# Spartan3_TestBoard_3.net
KiCad netlist of a schematic drawn in Altium Designer
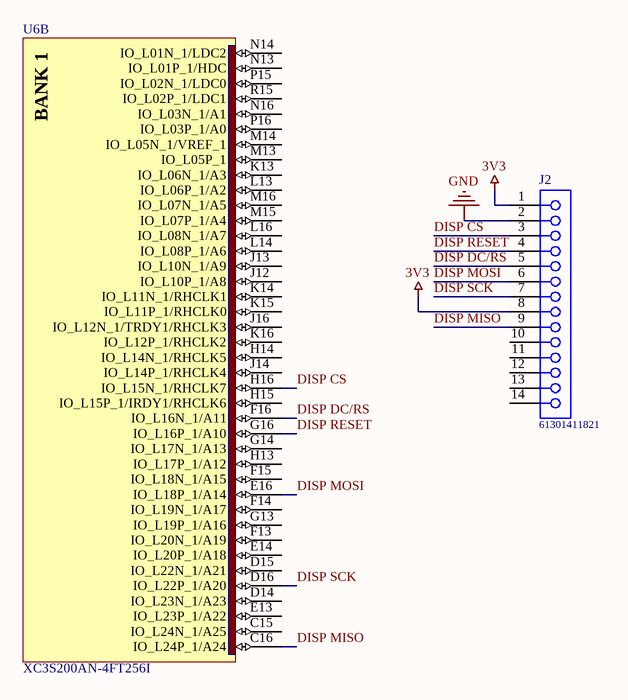
[diagram p0: Spartan3_TestBoard_3.SchDoc]

(export (version "E")
  (design (tool "Eeschema 10.0.6"))
  (components
    (comp (ref "J2")
      (value "61301411821")
      (footprint "61301411821")
      (description "WR-PHD Socket Header, THT, pitch 2.54mm, Single Row, Vertical, 14p")
      (fields (field (name "MANUFACTURER") "Wurth Elektronik"))
      (libsource (lib "61300311021_Altium_WR-PHD_rev20a") (part "61301411821"))
    )
    (comp (ref "U6")
      (value "XC3S200AN-4FT256I")
      (footprint "XC3S200AN-4FT256I")
      (libsource (lib "XC3S200AN-4FT256I") (part "XC3S200AN-4FT256I"))
    )
  )
  (nets
    (net (code "1") (name "/DISP CS") (class "Default")
      (node (ref "J2") (pin "3") (pinfunction "3_3") (pintype "passive"))
      (node (ref "U6") (pin "H16") (pinfunction "IO_L15N_1/RHCLK7_H16") (pintype "bidirectional"))
    )
    (net (code "2") (name "/DISP DC{slash}RS") (class "Default")
      (node (ref "J2") (pin "5") (pinfunction "5_5") (pintype "passive"))
      (node (ref "U6") (pin "F16") (pinfunction "IO_L16N_1/A11_F16") (pintype "bidirectional"))
    )
    (net (code "3") (name "/DISP MISO") (class "Default")
      (node (ref "J2") (pin "9") (pinfunction "9_9") (pintype "passive"))
      (node (ref "U6") (pin "C16") (pinfunction "IO_L24P_1/A24_C16") (pintype "bidirectional"))
    )
    (net (code "4") (name "/DISP MOSI") (class "Default")
      (node (ref "J2") (pin "6") (pinfunction "6_6") (pintype "passive"))
      (node (ref "U6") (pin "E16") (pinfunction "IO_L18P_1/A14_E16") (pintype "bidirectional"))
    )
    (net (code "5") (name "/DISP RESET") (class "Default")
      (node (ref "J2") (pin "4") (pinfunction "4_4") (pintype "passive"))
      (node (ref "U6") (pin "G16") (pinfunction "IO_L16P_1/A10_G16") (pintype "bidirectional"))
    )
    (net (code "6") (name "/DISP SCK") (class "Default")
      (node (ref "J2") (pin "7") (pinfunction "7_7") (pintype "passive"))
      (node (ref "U6") (pin "D16") (pinfunction "IO_L22P_1/A20_D16") (pintype "bidirectional"))
    )
    (net (code "7") (name "3V3") (class "Default")
      (node (ref "J2") (pin "1") (pinfunction "1_1") (pintype "passive"))
      (node (ref "J2") (pin "8") (pinfunction "8_8") (pintype "passive"))
    )
    (net (code "8") (name "GND") (class "Default")
      (node (ref "J2") (pin "2") (pinfunction "2_2") (pintype "passive"))
    )
    (net (code "9") (name "unconnected-(J2-Pad10)") (class "Default")
      (node (ref "J2") (pin "10") (pinfunction "10_10") (pintype "passive"))
    )
    (net (code "10") (name "unconnected-(J2-Pad11)") (class "Default")
      (node (ref "J2") (pin "11") (pinfunction "11_11") (pintype "passive"))
    )
    (net (code "11") (name "unconnected-(J2-Pad12)") (class "Default")
      (node (ref "J2") (pin "12") (pinfunction "12_12") (pintype "passive"))
    )
    (net (code "12") (name "unconnected-(J2-Pad13)") (class "Default")
      (node (ref "J2") (pin "13") (pinfunction "13_13") (pintype "passive"))
    )
    (net (code "13") (name "unconnected-(J2-Pad14)") (class "Default")
      (node (ref "J2") (pin "14") (pinfunction "14_14") (pintype "passive"))
    )
    (net (code "14") (name "unconnected-(U6B-IO_L01N_1{slash}LDC2-PadN14)") (class "Default")
      (node (ref "U6") (pin "N14") (pinfunction "IO_L01N_1/LDC2_N14") (pintype "bidirectional"))
    )
    (net (code "15") (name "unconnected-(U6B-IO_L01P_1{slash}HDC-PadN13)") (class "Default")
      (node (ref "U6") (pin "N13") (pinfunction "IO_L01P_1/HDC_N13") (pintype "bidirectional"))
    )
    (net (code "16") (name "unconnected-(U6B-IO_L02N_1{slash}LDC0-PadP15)") (class "Default")
      (node (ref "U6") (pin "P15") (pinfunction "IO_L02N_1/LDC0_P15") (pintype "bidirectional"))
    )
    (net (code "17") (name "unconnected-(U6B-IO_L02P_1{slash}LDC1-PadR15)") (class "Default")
      (node (ref "U6") (pin "R15") (pinfunction "IO_L02P_1/LDC1_R15") (pintype "bidirectional"))
    )
    (net (code "18") (name "unconnected-(U6B-IO_L03N_1{slash}A1-PadN16)") (class "Default")
      (node (ref "U6") (pin "N16") (pinfunction "IO_L03N_1/A1_N16") (pintype "bidirectional"))
    )
    (net (code "19") (name "unconnected-(U6B-IO_L03P_1{slash}A0-PadP16)") (class "Default")
      (node (ref "U6") (pin "P16") (pinfunction "IO_L03P_1/A0_P16") (pintype "bidirectional"))
    )
    (net (code "20") (name "unconnected-(U6B-IO_L05N_1{slash}VREF_1-PadM14)") (class "Default")
      (node (ref "U6") (pin "M14") (pinfunction "IO_L05N_1/VREF_1_M14") (pintype "bidirectional"))
    )
    (net (code "21") (name "unconnected-(U6B-IO_L05P_1-PadM13)") (class "Default")
      (node (ref "U6") (pin "M13") (pinfunction "IO_L05P_1_M13") (pintype "bidirectional"))
    )
    (net (code "22") (name "unconnected-(U6B-IO_L06N_1{slash}A3-PadK13)") (class "Default")
      (node (ref "U6") (pin "K13") (pinfunction "IO_L06N_1/A3_K13") (pintype "bidirectional"))
    )
    (net (code "23") (name "unconnected-(U6B-IO_L06P_1{slash}A2-PadL13)") (class "Default")
      (node (ref "U6") (pin "L13") (pinfunction "IO_L06P_1/A2_L13") (pintype "bidirectional"))
    )
    (net (code "24") (name "unconnected-(U6B-IO_L07N_1{slash}A5-PadM16)") (class "Default")
      (node (ref "U6") (pin "M16") (pinfunction "IO_L07N_1/A5_M16") (pintype "bidirectional"))
    )
    (net (code "25") (name "unconnected-(U6B-IO_L07P_1{slash}A4-PadM15)") (class "Default")
      (node (ref "U6") (pin "M15") (pinfunction "IO_L07P_1/A4_M15") (pintype "bidirectional"))
    )
    (net (code "26") (name "unconnected-(U6B-IO_L08N_1{slash}A7-PadL16)") (class "Default")
      (node (ref "U6") (pin "L16") (pinfunction "IO_L08N_1/A7_L16") (pintype "bidirectional"))
    )
    (net (code "27") (name "unconnected-(U6B-IO_L08P_1{slash}A6-PadL14)") (class "Default")
      (node (ref "U6") (pin "L14") (pinfunction "IO_L08P_1/A6_L14") (pintype "bidirectional"))
    )
    (net (code "28") (name "unconnected-(U6B-IO_L10N_1{slash}A9-PadJ13)") (class "Default")
      (node (ref "U6") (pin "J13") (pinfunction "IO_L10N_1/A9_J13") (pintype "bidirectional"))
    )
    (net (code "29") (name "unconnected-(U6B-IO_L10P_1{slash}A8-PadJ12)") (class "Default")
      (node (ref "U6") (pin "J12") (pinfunction "IO_L10P_1/A8_J12") (pintype "bidirectional"))
    )
    (net (code "30") (name "unconnected-(U6B-IO_L11N_1{slash}RHCLK1-PadK14)") (class "Default")
      (node (ref "U6") (pin "K14") (pinfunction "IO_L11N_1/RHCLK1_K14") (pintype "bidirectional"))
    )
    (net (code "31") (name "unconnected-(U6B-IO_L11P_1{slash}RHCLK0-PadK15)") (class "Default")
      (node (ref "U6") (pin "K15") (pinfunction "IO_L11P_1/RHCLK0_K15") (pintype "bidirectional"))
    )
    (net (code "32") (name "unconnected-(U6B-IO_L12N_1{slash}TRDY1{slash}RHCLK3-PadJ16)") (class "Default")
      (node (ref "U6") (pin "J16") (pinfunction "IO_L12N_1/TRDY1/RHCLK3_J16") (pintype "bidirectional"))
    )
    (net (code "33") (name "unconnected-(U6B-IO_L12P_1{slash}RHCLK2-PadK16)") (class "Default")
      (node (ref "U6") (pin "K16") (pinfunction "IO_L12P_1/RHCLK2_K16") (pintype "bidirectional"))
    )
    (net (code "34") (name "unconnected-(U6B-IO_L14N_1{slash}RHCLK5-PadH14)") (class "Default")
      (node (ref "U6") (pin "H14") (pinfunction "IO_L14N_1/RHCLK5_H14") (pintype "bidirectional"))
    )
    (net (code "35") (name "unconnected-(U6B-IO_L14P_1{slash}RHCLK4-PadJ14)") (class "Default")
      (node (ref "U6") (pin "J14") (pinfunction "IO_L14P_1/RHCLK4_J14") (pintype "bidirectional"))
    )
    (net (code "36") (name "unconnected-(U6B-IO_L15P_1{slash}IRDY1{slash}RHCLK6-PadH15)") (class "Default")
      (node (ref "U6") (pin "H15") (pinfunction "IO_L15P_1/IRDY1/RHCLK6_H15") (pintype "bidirectional"))
    )
    (net (code "37") (name "unconnected-(U6B-IO_L17N_1{slash}A13-PadG14)") (class "Default")
      (node (ref "U6") (pin "G14") (pinfunction "IO_L17N_1/A13_G14") (pintype "bidirectional"))
    )
    (net (code "38") (name "unconnected-(U6B-IO_L17P_1{slash}A12-PadH13)") (class "Default")
      (node (ref "U6") (pin "H13") (pinfunction "IO_L17P_1/A12_H13") (pintype "bidirectional"))
    )
    (net (code "39") (name "unconnected-(U6B-IO_L18N_1{slash}A15-PadF15)") (class "Default")
      (node (ref "U6") (pin "F15") (pinfunction "IO_L18N_1/A15_F15") (pintype "bidirectional"))
    )
    (net (code "40") (name "unconnected-(U6B-IO_L19N_1{slash}A17-PadF14)") (class "Default")
      (node (ref "U6") (pin "F14") (pinfunction "IO_L19N_1/A17_F14") (pintype "bidirectional"))
    )
    (net (code "41") (name "unconnected-(U6B-IO_L19P_1{slash}A16-PadG13)") (class "Default")
      (node (ref "U6") (pin "G13") (pinfunction "IO_L19P_1/A16_G13") (pintype "bidirectional"))
    )
    (net (code "42") (name "unconnected-(U6B-IO_L20N_1{slash}A19-PadF13)") (class "Default")
      (node (ref "U6") (pin "F13") (pinfunction "IO_L20N_1/A19_F13") (pintype "bidirectional"))
    )
    (net (code "43") (name "unconnected-(U6B-IO_L20P_1{slash}A18-PadE14)") (class "Default")
      (node (ref "U6") (pin "E14") (pinfunction "IO_L20P_1/A18_E14") (pintype "bidirectional"))
    )
    (net (code "44") (name "unconnected-(U6B-IO_L22N_1{slash}A21-PadD15)") (class "Default")
      (node (ref "U6") (pin "D15") (pinfunction "IO_L22N_1/A21_D15") (pintype "bidirectional"))
    )
    (net (code "45") (name "unconnected-(U6B-IO_L23N_1{slash}A23-PadD14)") (class "Default")
      (node (ref "U6") (pin "D14") (pinfunction "IO_L23N_1/A23_D14") (pintype "bidirectional"))
    )
    (net (code "46") (name "unconnected-(U6B-IO_L23P_1{slash}A22-PadE13)") (class "Default")
      (node (ref "U6") (pin "E13") (pinfunction "IO_L23P_1/A22_E13") (pintype "bidirectional"))
    )
    (net (code "47") (name "unconnected-(U6B-IO_L24N_1{slash}A25-PadC15)") (class "Default")
      (node (ref "U6") (pin "C15") (pinfunction "IO_L24N_1/A25_C15") (pintype "bidirectional"))
    )
  )
)
